# card.net
KiCad netlist of a schematic drawn in EAGLE
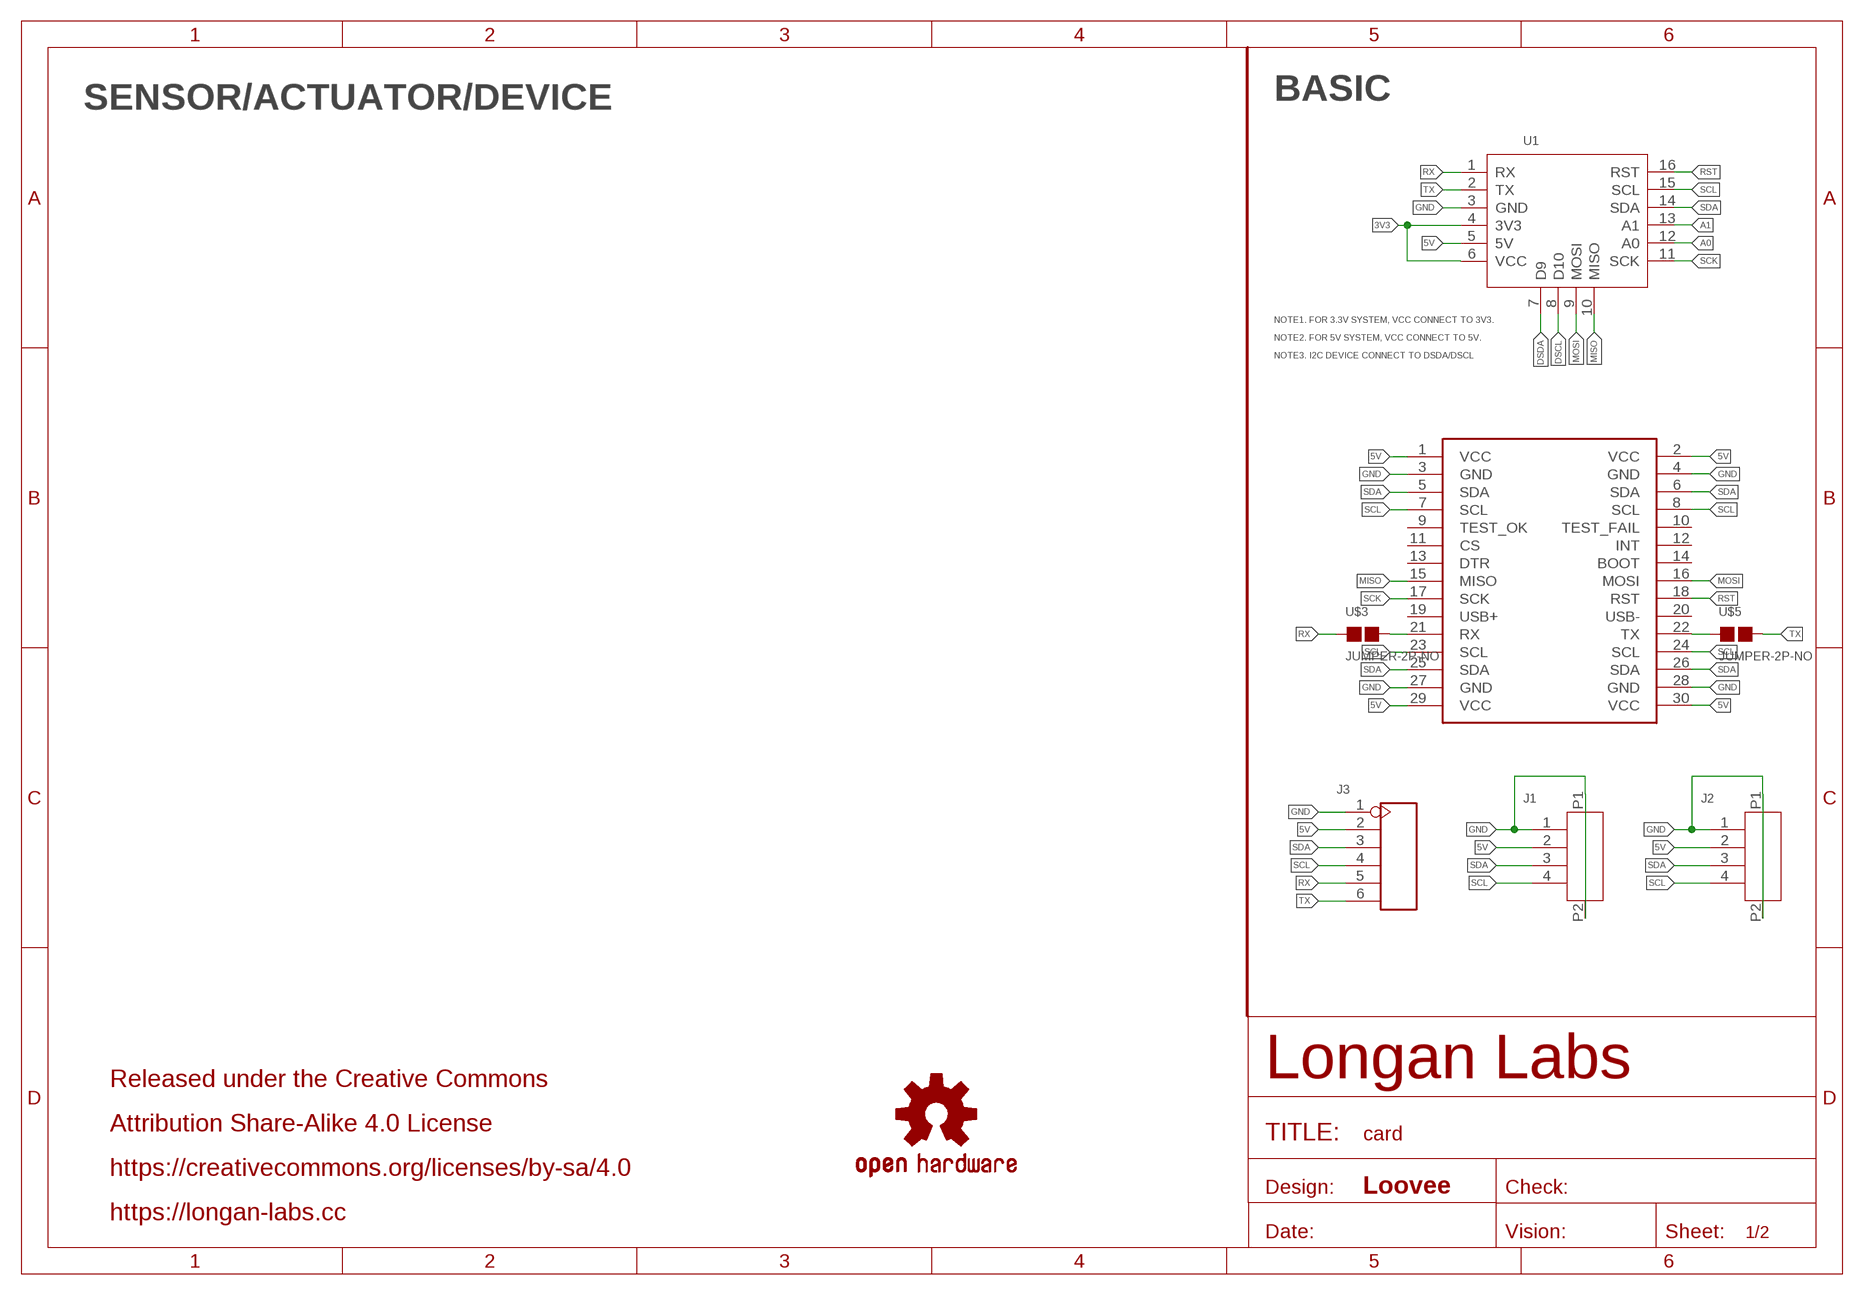
[diagram p0: schematic, sheet 1]

(export (version "E")
  (design (tool "Eeschema 10.0.6"))
  (components
    (comp (ref "J1")
      (value "HEADER-4P-1.0")
      (footprint "eagle-import:4P-1.0-90D")
      (libsource (lib "eagle-import") (part "HEADER-4P-1.0"))
    )
    (comp (ref "J2")
      (value "HEADER-4P-1.0")
      (footprint "eagle-import:4P-1.0-90D")
      (libsource (lib "eagle-import") (part "HEADER-4P-1.0"))
    )
    (comp (ref "J3")
      (value "HEADER-6P-55/35MIL")
      (footprint "eagle-import:H6-2.54")
      (libsource (lib "eagle-import") (part "HEADER-6P-55/35MIL"))
    )
    (comp (ref "LOGO2")
      (value "OSHW-LOGOS")
      (footprint "eagle-import:OSHW-LOGO-S")
      (libsource (lib "eagle-import") (part "OSHW-LOGOS"))
    )
    (comp (ref "MOUDLE1")
      (value "MOUDLE-2X15P-2.54'BOARD'")
      (footprint "eagle-import:MOUDLE-2X15P-2.54")
      (libsource (lib "eagle-import") (part "MOUDLE-2X15P-2.54'BOARD'"))
    )
    (comp (ref "U$3")
      (value "JUMPER-2P-NO")
      (footprint "eagle-import:2P-SMD-NO")
      (libsource (lib "eagle-import") (part "JUMPER-2P-NO"))
    )
    (comp (ref "U$5")
      (value "JUMPER-2P-NO")
      (footprint "eagle-import:2P-SMD-NO")
      (libsource (lib "eagle-import") (part "JUMPER-2P-NO"))
    )
    (comp (ref "U1")
      (value "MOUDLE-CARDS")
      (footprint "eagle-import:16P-2.0-CARDS")
      (libsource (lib "eagle-import") (part "MOUDLE-CARDS"))
    )
  )
  (nets
    (net (code "1") (name "3V3") (class "Default")
      (node (ref "U1") (pin "4") (pinfunction "3V3_4") (pintype "bidirectional"))
      (node (ref "U1") (pin "6") (pinfunction "VCC_6") (pintype "bidirectional"))
    )
    (net (code "2") (name "5V") (class "Default")
      (node (ref "J1") (pin "2") (pinfunction "2_2") (pintype "bidirectional"))
      (node (ref "J2") (pin "2") (pinfunction "2_2") (pintype "bidirectional"))
      (node (ref "J3") (pin "2") (pinfunction "2_2") (pintype "bidirectional"))
      (node (ref "MOUDLE1") (pin "1") (pinfunction "VCC_1") (pintype "bidirectional"))
      (node (ref "MOUDLE1") (pin "2") (pinfunction "VCC_2") (pintype "bidirectional"))
      (node (ref "MOUDLE1") (pin "29") (pinfunction "VCC_29") (pintype "bidirectional"))
      (node (ref "MOUDLE1") (pin "30") (pinfunction "VCC_30") (pintype "bidirectional"))
      (node (ref "U1") (pin "5") (pinfunction "5V_5") (pintype "bidirectional"))
    )
    (net (code "3") (name "A0") (class "Default")
      (node (ref "U1") (pin "12") (pinfunction "A0_12") (pintype "bidirectional"))
    )
    (net (code "4") (name "A1") (class "Default")
      (node (ref "U1") (pin "13") (pinfunction "A1_13") (pintype "bidirectional"))
    )
    (net (code "5") (name "DSCL") (class "Default")
      (node (ref "U1") (pin "8") (pinfunction "D10_8") (pintype "bidirectional"))
    )
    (net (code "6") (name "DSDA") (class "Default")
      (node (ref "U1") (pin "7") (pinfunction "D9_7") (pintype "bidirectional"))
    )
    (net (code "7") (name "GND") (class "Default")
      (node (ref "J1") (pin "1") (pinfunction "1_1") (pintype "bidirectional"))
      (node (ref "J1") (pin "P1") (pinfunction "P1_P1") (pintype "bidirectional"))
      (node (ref "J1") (pin "P2") (pinfunction "P2_P2") (pintype "bidirectional"))
      (node (ref "J2") (pin "1") (pinfunction "1_1") (pintype "bidirectional"))
      (node (ref "J2") (pin "P1") (pinfunction "P1_P1") (pintype "bidirectional"))
      (node (ref "J2") (pin "P2") (pinfunction "P2_P2") (pintype "bidirectional"))
      (node (ref "J3") (pin "1") (pinfunction "1_1") (pintype "bidirectional"))
      (node (ref "MOUDLE1") (pin "27") (pinfunction "GND_27") (pintype "bidirectional"))
      (node (ref "MOUDLE1") (pin "28") (pinfunction "GND_28") (pintype "bidirectional"))
      (node (ref "MOUDLE1") (pin "3") (pinfunction "GND_3") (pintype "bidirectional"))
      (node (ref "MOUDLE1") (pin "4") (pinfunction "GND_4") (pintype "bidirectional"))
      (node (ref "U1") (pin "3") (pinfunction "GND_3") (pintype "bidirectional"))
    )
    (net (code "8") (name "MISO") (class "Default")
      (node (ref "MOUDLE1") (pin "15") (pinfunction "MISO_15") (pintype "bidirectional"))
      (node (ref "U1") (pin "10") (pinfunction "MISO_10") (pintype "bidirectional"))
    )
    (net (code "9") (name "MOSI") (class "Default")
      (node (ref "MOUDLE1") (pin "16") (pinfunction "MOSI_16") (pintype "bidirectional"))
      (node (ref "U1") (pin "9") (pinfunction "MOSI_9") (pintype "bidirectional"))
    )
    (net (code "10") (name "Net-(MOUDLE1-RX)") (class "Default")
      (node (ref "MOUDLE1") (pin "21") (pinfunction "RX_21") (pintype "bidirectional"))
      (node (ref "U$3") (pin "2") (pinfunction "2_2") (pintype "bidirectional"))
    )
    (net (code "11") (name "Net-(MOUDLE1-TX)") (class "Default")
      (node (ref "MOUDLE1") (pin "22") (pinfunction "TX_22") (pintype "bidirectional"))
      (node (ref "U$5") (pin "1") (pinfunction "1_1") (pintype "bidirectional"))
    )
    (net (code "12") (name "RST") (class "Default")
      (node (ref "MOUDLE1") (pin "18") (pinfunction "RST_18") (pintype "bidirectional"))
      (node (ref "U1") (pin "16") (pinfunction "RST_16") (pintype "bidirectional"))
    )
    (net (code "13") (name "RX") (class "Default")
      (node (ref "J3") (pin "5") (pinfunction "5_5") (pintype "bidirectional"))
      (node (ref "U$3") (pin "1") (pinfunction "1_1") (pintype "bidirectional"))
      (node (ref "U1") (pin "1") (pinfunction "RX_1") (pintype "bidirectional"))
    )
    (net (code "14") (name "SCK") (class "Default")
      (node (ref "MOUDLE1") (pin "17") (pinfunction "SCK_17") (pintype "bidirectional"))
      (node (ref "U1") (pin "11") (pinfunction "SCK_11") (pintype "bidirectional"))
    )
    (net (code "15") (name "SCL") (class "Default")
      (node (ref "J1") (pin "4") (pinfunction "4_4") (pintype "bidirectional"))
      (node (ref "J2") (pin "4") (pinfunction "4_4") (pintype "bidirectional"))
      (node (ref "J3") (pin "4") (pinfunction "4_4") (pintype "bidirectional"))
      (node (ref "MOUDLE1") (pin "23") (pinfunction "SCL_23") (pintype "bidirectional"))
      (node (ref "MOUDLE1") (pin "24") (pinfunction "SCL_24") (pintype "bidirectional"))
      (node (ref "MOUDLE1") (pin "7") (pinfunction "SCL_7") (pintype "bidirectional"))
      (node (ref "MOUDLE1") (pin "8") (pinfunction "SCL_8") (pintype "bidirectional"))
      (node (ref "U1") (pin "15") (pinfunction "SCL_15") (pintype "bidirectional"))
    )
    (net (code "16") (name "SDA") (class "Default")
      (node (ref "J1") (pin "3") (pinfunction "3_3") (pintype "bidirectional"))
      (node (ref "J2") (pin "3") (pinfunction "3_3") (pintype "bidirectional"))
      (node (ref "J3") (pin "3") (pinfunction "3_3") (pintype "bidirectional"))
      (node (ref "MOUDLE1") (pin "25") (pinfunction "SDA_25") (pintype "bidirectional"))
      (node (ref "MOUDLE1") (pin "26") (pinfunction "SDA_26") (pintype "bidirectional"))
      (node (ref "MOUDLE1") (pin "5") (pinfunction "SDA_5") (pintype "bidirectional"))
      (node (ref "MOUDLE1") (pin "6") (pinfunction "SDA_6") (pintype "bidirectional"))
      (node (ref "U1") (pin "14") (pinfunction "SDA_14") (pintype "bidirectional"))
    )
    (net (code "17") (name "TX") (class "Default")
      (node (ref "J3") (pin "6") (pinfunction "6_6") (pintype "bidirectional"))
      (node (ref "U$5") (pin "2") (pinfunction "2_2") (pintype "bidirectional"))
      (node (ref "U1") (pin "2") (pinfunction "TX_2") (pintype "bidirectional"))
    )
    (net (code "18") (name "unconnected-(MOUDLE1-BOOT-Pad14)") (class "Default")
      (node (ref "MOUDLE1") (pin "14") (pinfunction "BOOT_14") (pintype "bidirectional"))
    )
    (net (code "19") (name "unconnected-(MOUDLE1-CS-Pad11)") (class "Default")
      (node (ref "MOUDLE1") (pin "11") (pinfunction "CS_11") (pintype "bidirectional"))
    )
    (net (code "20") (name "unconnected-(MOUDLE1-DTR-Pad13)") (class "Default")
      (node (ref "MOUDLE1") (pin "13") (pinfunction "DTR_13") (pintype "bidirectional"))
    )
    (net (code "21") (name "unconnected-(MOUDLE1-INT-Pad12)") (class "Default")
      (node (ref "MOUDLE1") (pin "12") (pinfunction "INT_12") (pintype "bidirectional"))
    )
    (net (code "22") (name "unconnected-(MOUDLE1-TEST_FAIL-Pad10)") (class "Default")
      (node (ref "MOUDLE1") (pin "10") (pinfunction "TEST_FAIL_10") (pintype "bidirectional"))
    )
    (net (code "23") (name "unconnected-(MOUDLE1-TEST_OK-Pad9)") (class "Default")
      (node (ref "MOUDLE1") (pin "9") (pinfunction "TEST_OK_9") (pintype "bidirectional"))
    )
    (net (code "24") (name "unconnected-(MOUDLE1-USB+-Pad19)") (class "Default")
      (node (ref "MOUDLE1") (pin "19") (pinfunction "USB+_19") (pintype "bidirectional"))
    )
    (net (code "25") (name "unconnected-(MOUDLE1-USB--Pad20)") (class "Default")
      (node (ref "MOUDLE1") (pin "20") (pinfunction "USB-_20") (pintype "bidirectional"))
    )
  )
)
